# esp-adap.net
KiCad netlist of a schematic drawn in EAGLE
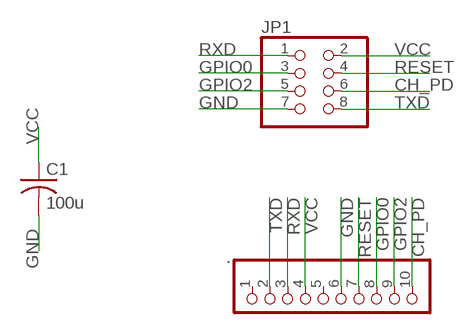
[diagram p0: schematic, sheet 1]

(export (version "E")
  (design (tool "Eeschema 10.0.6"))
  (components
    (comp (ref ".")
      (value "PINHD-1X10")
      (footprint "eagle-import:1X10")
      (libsource (lib "eagle-import") (part "PINHD-1X10"))
    )
    (comp (ref "C1")
      (value "100u")
      (footprint "eagle-import:C1206K")
      (libsource (lib "eagle-import") (part "C-USC1206K"))
    )
    (comp (ref "JP1")
      (value "PINHD-2X4")
      (footprint "eagle-import:2X04")
      (libsource (lib "eagle-import") (part "PINHD-2X4"))
    )
  )
  (nets
    (net (code "1") (name "/CH_PD") (class "Default")
      (node (ref ".") (pin "10") (pinfunction "10_10") (pintype "passive"))
      (node (ref "JP1") (pin "6") (pinfunction "6_6") (pintype "passive"))
    )
    (net (code "2") (name "/GND") (class "Default")
      (node (ref ".") (pin "6") (pinfunction "6_6") (pintype "passive"))
      (node (ref "C1") (pin "2") (pinfunction "2_2") (pintype "passive"))
      (node (ref "JP1") (pin "7") (pinfunction "7_7") (pintype "passive"))
    )
    (net (code "3") (name "/GPIO0") (class "Default")
      (node (ref ".") (pin "8") (pinfunction "8_8") (pintype "passive"))
      (node (ref "JP1") (pin "3") (pinfunction "3_3") (pintype "passive"))
    )
    (net (code "4") (name "/GPIO2") (class "Default")
      (node (ref ".") (pin "9") (pinfunction "9_9") (pintype "passive"))
      (node (ref "JP1") (pin "5") (pinfunction "5_5") (pintype "passive"))
    )
    (net (code "5") (name "/RESET") (class "Default")
      (node (ref ".") (pin "7") (pinfunction "7_7") (pintype "passive"))
      (node (ref "JP1") (pin "4") (pinfunction "4_4") (pintype "passive"))
    )
    (net (code "6") (name "/RXD") (class "Default")
      (node (ref ".") (pin "3") (pinfunction "3_3") (pintype "passive"))
      (node (ref "JP1") (pin "1") (pinfunction "1_1") (pintype "passive"))
    )
    (net (code "7") (name "/TXD") (class "Default")
      (node (ref ".") (pin "2") (pinfunction "2_2") (pintype "passive"))
      (node (ref "JP1") (pin "8") (pinfunction "8_8") (pintype "passive"))
    )
    (net (code "8") (name "/VCC") (class "Default")
      (node (ref ".") (pin "4") (pinfunction "4_4") (pintype "passive"))
      (node (ref "C1") (pin "1") (pinfunction "1_1") (pintype "passive"))
      (node (ref "JP1") (pin "2") (pinfunction "2_2") (pintype "passive"))
    )
    (net (code "9") (name "unconnected-(.-Pad1)") (class "Default")
      (node (ref ".") (pin "1") (pinfunction "1_1") (pintype "passive"))
    )
    (net (code "10") (name "unconnected-(.-Pad5)") (class "Default")
      (node (ref ".") (pin "5") (pinfunction "5_5") (pintype "passive"))
    )
  )
)
